# CAN.net
KiCad netlist of a schematic drawn in Altium Designer
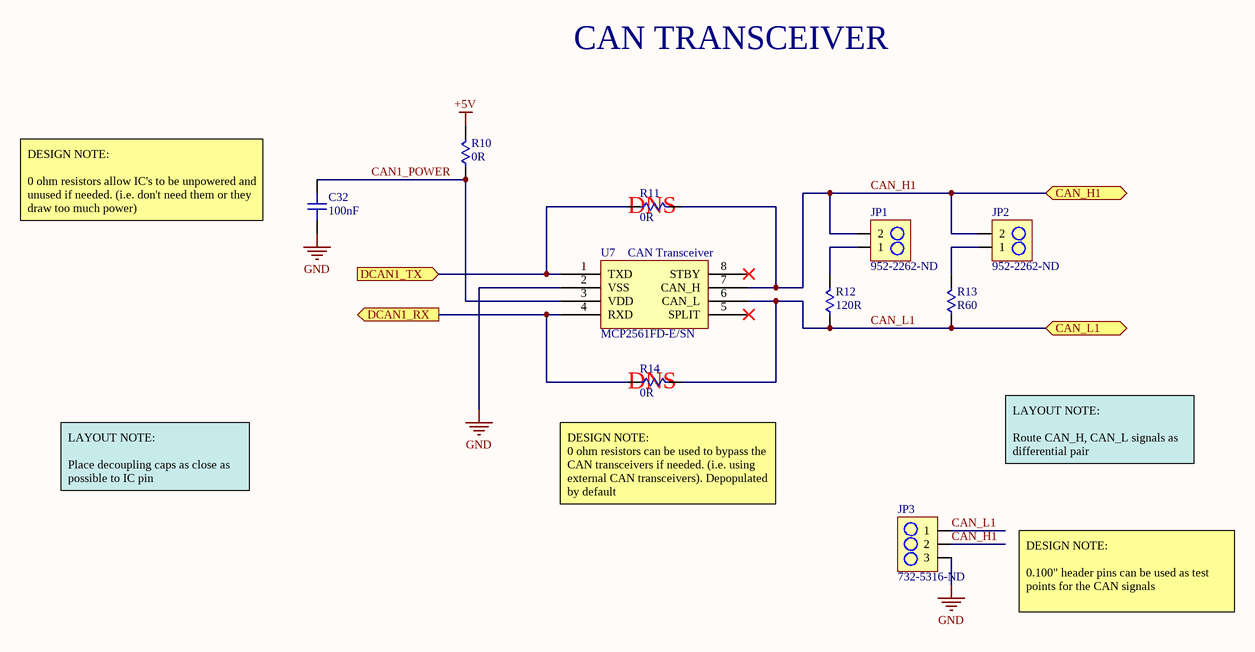
[diagram p0: CAN.SchDoc]

(export (version "E")
  (design (tool "Eeschema 10.0.6"))
  (components
    (comp (ref "C32")
      (value "100nF")
      (footprint "C0402")
      (description "CAP MLCC 0.1uF 10V X5R 0402 20% SMD 0402 85C Paper T/R")
      (fields
        (field (name "MANUFACTURER") "Samsung")
        (field (name "MANUFACTURER PART NUMBER") "CL05A104MP5NNNC")
      )
      (libsource (lib "PHANTOM_LIBRARY") (part "CL05A104MP5NNNC"))
    )
    (comp (ref "JP1")
      (value "952-2262-ND")
      (footprint "2PIN_HEADER")
      (description "CONN_HeaderPins2pos Headers & Wire Housings 02 SIL VERTICAL PIN HEADER TIN")
      (fields (field (name "MANUFACTURER") "Harwin") (field (name "MANUFACTURER PART NUMBER") "M20-9990246"))
      (libsource (lib "PHANTOM_LIBRARY") (part "M20-9990246"))
    )
    (comp (ref "JP2")
      (value "952-2262-ND")
      (footprint "2PIN_HEADER")
      (description "CONN_HeaderPins2pos Headers & Wire Housings 02 SIL VERTICAL PIN HEADER TIN")
      (fields (field (name "MANUFACTURER") "Harwin") (field (name "MANUFACTURER PART NUMBER") "M20-9990246"))
      (libsource (lib "PHANTOM_LIBRARY") (part "M20-9990246"))
    )
    (comp (ref "JP3")
      (value "732-5316-ND")
      (footprint "3PIN_HEADER")
      (fields
        (field (name "MANUFACTURER") "Wurth Electronics")
        (field (name "MANUFACTURER PART NUMBER") "61300311121")
      )
      (libsource (lib "PHANTOM_LIBRARY") (part "61300311121"))
    )
    (comp (ref "R10")
      (value "0R")
      (footprint "R0402")
      (description "RES SMD 0 OHM 1/16W 0402")
      (fields
        (field (name "MANUFACTURER") "Yageo")
        (field (name "MANUFACTURER PART NUMBER") "RC0402JR-070RL")
      )
      (libsource (lib "PHANTOM_LIBRARY") (part "RC0402JR-070RL"))
    )
    (comp (ref "R11")
      (value "0R")
      (footprint "R0402")
      (description "RES SMD 0 OHM 1/16W 0402")
      (fields
        (field (name "MANUFACTURER") "Yageo")
        (field (name "MANUFACTURER PART NUMBER") "RC0402JR-070RL")
      )
      (libsource (lib "PHANTOM_LIBRARY") (part "RC0402JR-070RL"))
    )
    (comp (ref "R12")
      (value "120R")
      (footprint "R0402")
      (description "RES SMD 120 OHM 5% 0402 1/16W ±100ppm/C Molded SMD Paper T/R")
      (fields
        (field (name "MANUFACTURER") "Stackpole Electronics")
        (field (name "MANUFACTURER PART NUMBER") "RMCF0402JT120R")
      )
      (libsource (lib "PHANTOM_LIBRARY") (part "RMCF0402JT120R"))
    )
    (comp (ref "R13")
      (value "R60")
      (footprint "R0402")
      (description "RES SMD 60.4 OHM 1% 0402 1/16W 100ppm/C Molded SMD SMD Paper T/R")
      (fields
        (field (name "MANUFACTURER") "Stackpole Electronics")
        (field (name "MANUFACTURER PART NUMBER") "RMCF0402FT60R4")
      )
      (libsource (lib "PHANTOM_LIBRARY") (part "RMCF0402FT60R4"))
    )
    (comp (ref "R14")
      (value "0R")
      (footprint "R0402")
      (description "RES SMD 0 OHM 1/16W 0402")
      (fields
        (field (name "MANUFACTURER") "Yageo")
        (field (name "MANUFACTURER PART NUMBER") "RC0402JR-070RL")
      )
      (libsource (lib "PHANTOM_LIBRARY") (part "RC0402JR-070RL"))
    )
    (comp (ref "U7")
      (value "MCP2561FD-E/SN")
      (footprint "8-SOIC_MCP2561")
      (description "IC CAN Bus, Transceiver, CAN, 1, 1, 4.5 V, 5.5 V, SOIC")
      (fields (field (name "MANUFACTURER") "Microchip"))
      (libsource (lib "PHANTOM_LIBRARY") (part "MCP2561FD-E/SN"))
    )
  )
  (nets
    (net (code "1") (name "+5V") (class "Default")
      (node (ref "R10") (pin "2") (pinfunction "2_2") (pintype "passive"))
    )
    (net (code "2") (name "/CAN1_POWER") (class "Default")
      (node (ref "C32") (pin "2") (pinfunction "2_2") (pintype "passive"))
      (node (ref "R10") (pin "1") (pinfunction "1_1") (pintype "passive"))
      (node (ref "U7") (pin "3") (pinfunction "VDD_3") (pintype "passive"))
    )
    (net (code "3") (name "/CAN_H1") (class "Default")
      (node (ref "JP1") (pin "2") (pinfunction "2_2") (pintype "passive"))
      (node (ref "JP2") (pin "2") (pinfunction "2_2") (pintype "passive"))
      (node (ref "JP3") (pin "2") (pinfunction "2_2") (pintype "passive"))
      (node (ref "R11") (pin "2") (pinfunction "2_2") (pintype "passive"))
      (node (ref "U7") (pin "7") (pinfunction "CAN_H_7") (pintype "passive"))
    )
    (net (code "4") (name "/CAN_L1") (class "Default")
      (node (ref "JP3") (pin "1") (pinfunction "1_1") (pintype "passive"))
      (node (ref "R12") (pin "1") (pinfunction "1_1") (pintype "passive"))
      (node (ref "R13") (pin "1") (pinfunction "1_1") (pintype "passive"))
      (node (ref "R14") (pin "2") (pinfunction "2_2") (pintype "passive"))
      (node (ref "U7") (pin "6") (pinfunction "CAN_L_6") (pintype "passive"))
    )
    (net (code "5") (name "/DCAN1_RX") (class "Default")
      (node (ref "R14") (pin "1") (pinfunction "1_1") (pintype "passive"))
      (node (ref "U7") (pin "4") (pinfunction "RXD_4") (pintype "passive"))
    )
    (net (code "6") (name "/DCAN1_TX") (class "Default")
      (node (ref "R11") (pin "1") (pinfunction "1_1") (pintype "passive"))
      (node (ref "U7") (pin "1") (pinfunction "TXD_1") (pintype "passive"))
    )
    (net (code "7") (name "GND") (class "Default")
      (node (ref "C32") (pin "1") (pinfunction "1_1") (pintype "passive"))
      (node (ref "JP3") (pin "3") (pinfunction "3_3") (pintype "passive"))
      (node (ref "U7") (pin "2") (pinfunction "VSS_2") (pintype "passive"))
    )
    (net (code "8") (name "Net-(JP1-Pad1)") (class "Default")
      (node (ref "JP1") (pin "1") (pinfunction "1_1") (pintype "passive"))
      (node (ref "R12") (pin "2") (pinfunction "2_2") (pintype "passive"))
    )
    (net (code "9") (name "Net-(JP2-Pad1)") (class "Default")
      (node (ref "JP2") (pin "1") (pinfunction "1_1") (pintype "passive"))
      (node (ref "R13") (pin "2") (pinfunction "2_2") (pintype "passive"))
    )
    (net (code "10") (name "unconnected-(U7-SPLIT-Pad5)") (class "Default")
      (node (ref "U7") (pin "5") (pinfunction "SPLIT_5") (pintype "passive+no_connect"))
    )
    (net (code "11") (name "unconnected-(U7-STBY-Pad8)") (class "Default")
      (node (ref "U7") (pin "8") (pinfunction "STBY_8") (pintype "passive+no_connect"))
    )
  )
)
